# Connector-Side-1.net
KiCad netlist of a schematic drawn in Altium Designer
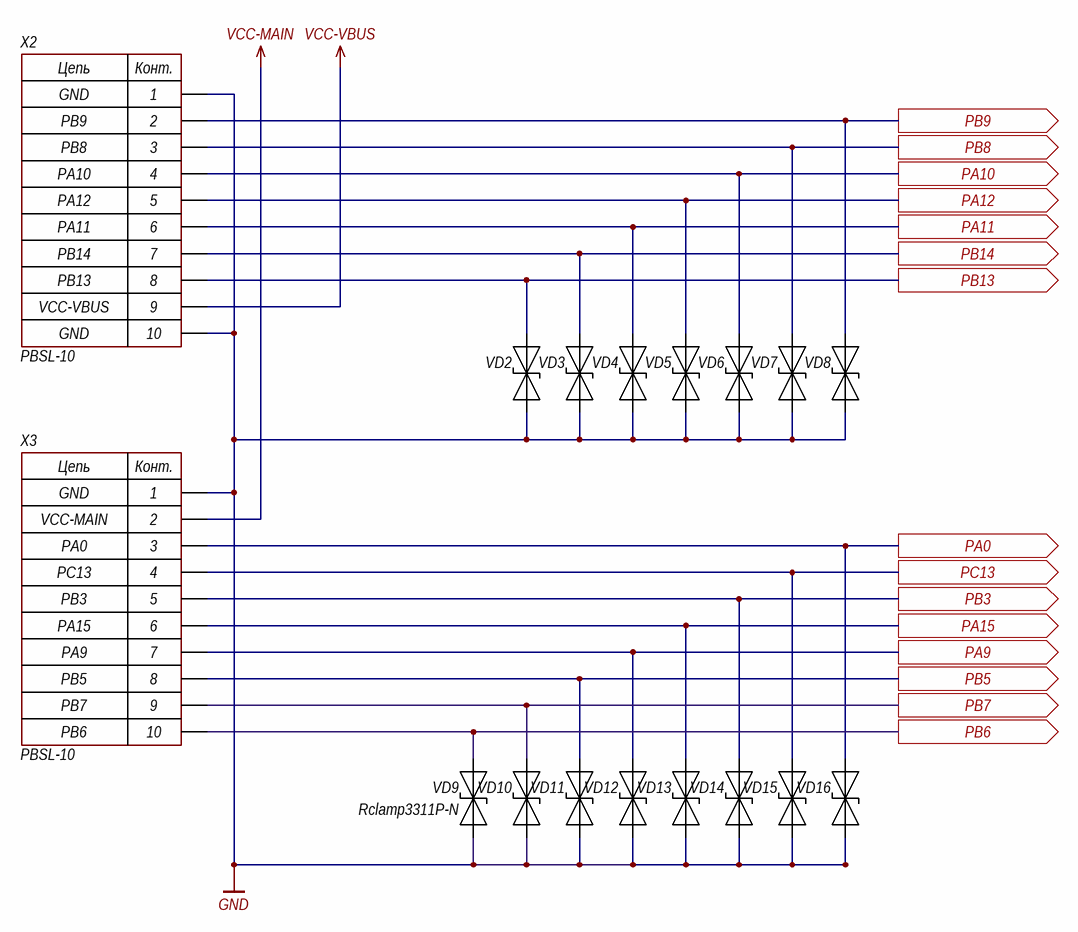
[diagram p0: Connector-Side-1.SchDoc]

(export (version "E")
  (design (tool "Eeschema 10.0.6"))
  (components
    (comp (ref "VD2")
      (value "Rclamp3311P-N")
      (footprint "DFN1006-2")
      (fields (field (name "MANUFACTURER") "BORN"))
      (libsource (lib "Diods") (part "TVS-diod"))
    )
    (comp (ref "VD3")
      (value "Rclamp3311P-N")
      (footprint "DFN1006-2")
      (fields (field (name "MANUFACTURER") "BORN"))
      (libsource (lib "Diods") (part "TVS-diod"))
    )
    (comp (ref "VD4")
      (value "Rclamp3311P-N")
      (footprint "DFN1006-2")
      (fields (field (name "MANUFACTURER") "BORN"))
      (libsource (lib "Diods") (part "TVS-diod"))
    )
    (comp (ref "VD5")
      (value "Rclamp3311P-N")
      (footprint "DFN1006-2")
      (fields (field (name "MANUFACTURER") "BORN"))
      (libsource (lib "Diods") (part "TVS-diod"))
    )
    (comp (ref "VD6")
      (value "Rclamp3311P-N")
      (footprint "DFN1006-2")
      (fields (field (name "MANUFACTURER") "BORN"))
      (libsource (lib "Diods") (part "TVS-diod"))
    )
    (comp (ref "VD7")
      (value "Rclamp3311P-N")
      (footprint "DFN1006-2")
      (fields (field (name "MANUFACTURER") "BORN"))
      (libsource (lib "Diods") (part "TVS-diod"))
    )
    (comp (ref "VD8")
      (value "Rclamp3311P-N")
      (footprint "DFN1006-2")
      (fields (field (name "MANUFACTURER") "BORN"))
      (libsource (lib "Diods") (part "TVS-diod"))
    )
    (comp (ref "VD9")
      (value "Rclamp3311P-N")
      (footprint "DFN1006-2")
      (fields (field (name "MANUFACTURER") "BORN"))
      (libsource (lib "Diods") (part "TVS-diod"))
    )
    (comp (ref "VD10")
      (value "Rclamp3311P-N")
      (footprint "DFN1006-2")
      (fields (field (name "MANUFACTURER") "BORN"))
      (libsource (lib "Diods") (part "TVS-diod"))
    )
    (comp (ref "VD11")
      (value "Rclamp3311P-N")
      (footprint "DFN1006-2")
      (fields (field (name "MANUFACTURER") "BORN"))
      (libsource (lib "Diods") (part "TVS-diod"))
    )
    (comp (ref "VD12")
      (value "Rclamp3311P-N")
      (footprint "DFN1006-2")
      (fields (field (name "MANUFACTURER") "BORN"))
      (libsource (lib "Diods") (part "TVS-diod"))
    )
    (comp (ref "VD13")
      (value "Rclamp3311P-N")
      (footprint "DFN1006-2")
      (fields (field (name "MANUFACTURER") "BORN"))
      (libsource (lib "Diods") (part "TVS-diod"))
    )
    (comp (ref "VD14")
      (value "Rclamp3311P-N")
      (footprint "DFN1006-2")
      (fields (field (name "MANUFACTURER") "BORN"))
      (libsource (lib "Diods") (part "TVS-diod"))
    )
    (comp (ref "VD15")
      (value "Rclamp3311P-N")
      (footprint "DFN1006-2")
      (fields (field (name "MANUFACTURER") "BORN"))
      (libsource (lib "Diods") (part "TVS-diod"))
    )
    (comp (ref "VD16")
      (value "Rclamp3311P-N")
      (footprint "DFN1006-2")
      (fields (field (name "MANUFACTURER") "BORN"))
      (libsource (lib "Diods") (part "TVS-diod"))
    )
    (comp (ref "X2")
      (value "PBSL-10")
      (footprint "CON: PBSL-10")
      (libsource (lib "Connectors") (part "10-Connector"))
    )
    (comp (ref "X3")
      (value "PBSL-10")
      (footprint "CON: PBSL-10")
      (libsource (lib "Connectors") (part "10-Connector"))
    )
  )
  (nets
    (net (code "1") (name "/PA0") (class "Default")
      (node (ref "VD16") (pin "2") (pinfunction "C_2") (pintype "passive"))
      (node (ref "X3") (pin "3") (pinfunction "3_3") (pintype "passive"))
    )
    (net (code "2") (name "/PA9") (class "Default")
      (node (ref "VD12") (pin "2") (pinfunction "C_2") (pintype "passive"))
      (node (ref "X3") (pin "7") (pinfunction "7_7") (pintype "passive"))
    )
    (net (code "3") (name "/PA10") (class "Default")
      (node (ref "VD6") (pin "2") (pinfunction "C_2") (pintype "passive"))
      (node (ref "X2") (pin "4") (pinfunction "4_4") (pintype "passive"))
    )
    (net (code "4") (name "/PA11") (class "Default")
      (node (ref "VD4") (pin "2") (pinfunction "C_2") (pintype "passive"))
      (node (ref "X2") (pin "6") (pinfunction "6_6") (pintype "passive"))
    )
    (net (code "5") (name "/PA12") (class "Default")
      (node (ref "VD5") (pin "2") (pinfunction "C_2") (pintype "passive"))
      (node (ref "X2") (pin "5") (pinfunction "5_5") (pintype "passive"))
    )
    (net (code "6") (name "/PA15") (class "Default")
      (node (ref "VD13") (pin "2") (pinfunction "C_2") (pintype "passive"))
      (node (ref "X3") (pin "6") (pinfunction "6_6") (pintype "passive"))
    )
    (net (code "7") (name "/PB3") (class "Default")
      (node (ref "VD14") (pin "2") (pinfunction "C_2") (pintype "passive"))
      (node (ref "X3") (pin "5") (pinfunction "5_5") (pintype "passive"))
    )
    (net (code "8") (name "/PB5") (class "Default")
      (node (ref "VD11") (pin "2") (pinfunction "C_2") (pintype "passive"))
      (node (ref "X3") (pin "8") (pinfunction "8_8") (pintype "passive"))
    )
    (net (code "9") (name "/PB6") (class "Default")
      (node (ref "VD9") (pin "2") (pinfunction "C_2") (pintype "passive"))
      (node (ref "X3") (pin "10") (pinfunction "10_10") (pintype "passive"))
    )
    (net (code "10") (name "/PB7") (class "Default")
      (node (ref "VD10") (pin "2") (pinfunction "C_2") (pintype "passive"))
      (node (ref "X3") (pin "9") (pinfunction "9_9") (pintype "passive"))
    )
    (net (code "11") (name "/PB8") (class "Default")
      (node (ref "VD7") (pin "2") (pinfunction "C_2") (pintype "passive"))
      (node (ref "X2") (pin "3") (pinfunction "3_3") (pintype "passive"))
    )
    (net (code "12") (name "/PB9") (class "Default")
      (node (ref "VD8") (pin "2") (pinfunction "C_2") (pintype "passive"))
      (node (ref "X2") (pin "2") (pinfunction "2_2") (pintype "passive"))
    )
    (net (code "13") (name "/PB13") (class "Default")
      (node (ref "VD2") (pin "2") (pinfunction "C_2") (pintype "passive"))
      (node (ref "X2") (pin "8") (pinfunction "8_8") (pintype "passive"))
    )
    (net (code "14") (name "/PB14") (class "Default")
      (node (ref "VD3") (pin "2") (pinfunction "C_2") (pintype "passive"))
      (node (ref "X2") (pin "7") (pinfunction "7_7") (pintype "passive"))
    )
    (net (code "15") (name "/PC13") (class "Default")
      (node (ref "VD15") (pin "2") (pinfunction "C_2") (pintype "passive"))
      (node (ref "X3") (pin "4") (pinfunction "4_4") (pintype "passive"))
    )
    (net (code "16") (name "GND") (class "Default")
      (node (ref "VD10") (pin "1") (pinfunction "A_1") (pintype "passive"))
      (node (ref "VD11") (pin "1") (pinfunction "A_1") (pintype "passive"))
      (node (ref "VD12") (pin "1") (pinfunction "A_1") (pintype "passive"))
      (node (ref "VD13") (pin "1") (pinfunction "A_1") (pintype "passive"))
      (node (ref "VD14") (pin "1") (pinfunction "A_1") (pintype "passive"))
      (node (ref "VD15") (pin "1") (pinfunction "A_1") (pintype "passive"))
      (node (ref "VD16") (pin "1") (pinfunction "A_1") (pintype "passive"))
      (node (ref "VD2") (pin "1") (pinfunction "A_1") (pintype "passive"))
      (node (ref "VD3") (pin "1") (pinfunction "A_1") (pintype "passive"))
      (node (ref "VD4") (pin "1") (pinfunction "A_1") (pintype "passive"))
      (node (ref "VD5") (pin "1") (pinfunction "A_1") (pintype "passive"))
      (node (ref "VD6") (pin "1") (pinfunction "A_1") (pintype "passive"))
      (node (ref "VD7") (pin "1") (pinfunction "A_1") (pintype "passive"))
      (node (ref "VD8") (pin "1") (pinfunction "A_1") (pintype "passive"))
      (node (ref "VD9") (pin "1") (pinfunction "A_1") (pintype "passive"))
      (node (ref "X2") (pin "1") (pinfunction "1_1") (pintype "passive"))
      (node (ref "X2") (pin "10") (pinfunction "10_10") (pintype "passive"))
      (node (ref "X3") (pin "1") (pinfunction "1_1") (pintype "passive"))
    )
    (net (code "17") (name "VCC-MAIN") (class "Default")
      (node (ref "X3") (pin "2") (pinfunction "2_2") (pintype "passive"))
    )
    (net (code "18") (name "VCC-VBUS") (class "Default")
      (node (ref "X2") (pin "9") (pinfunction "9_9") (pintype "passive"))
    )
  )
)
